# example.net
KiCad netlist of a schematic drawn in EAGLE
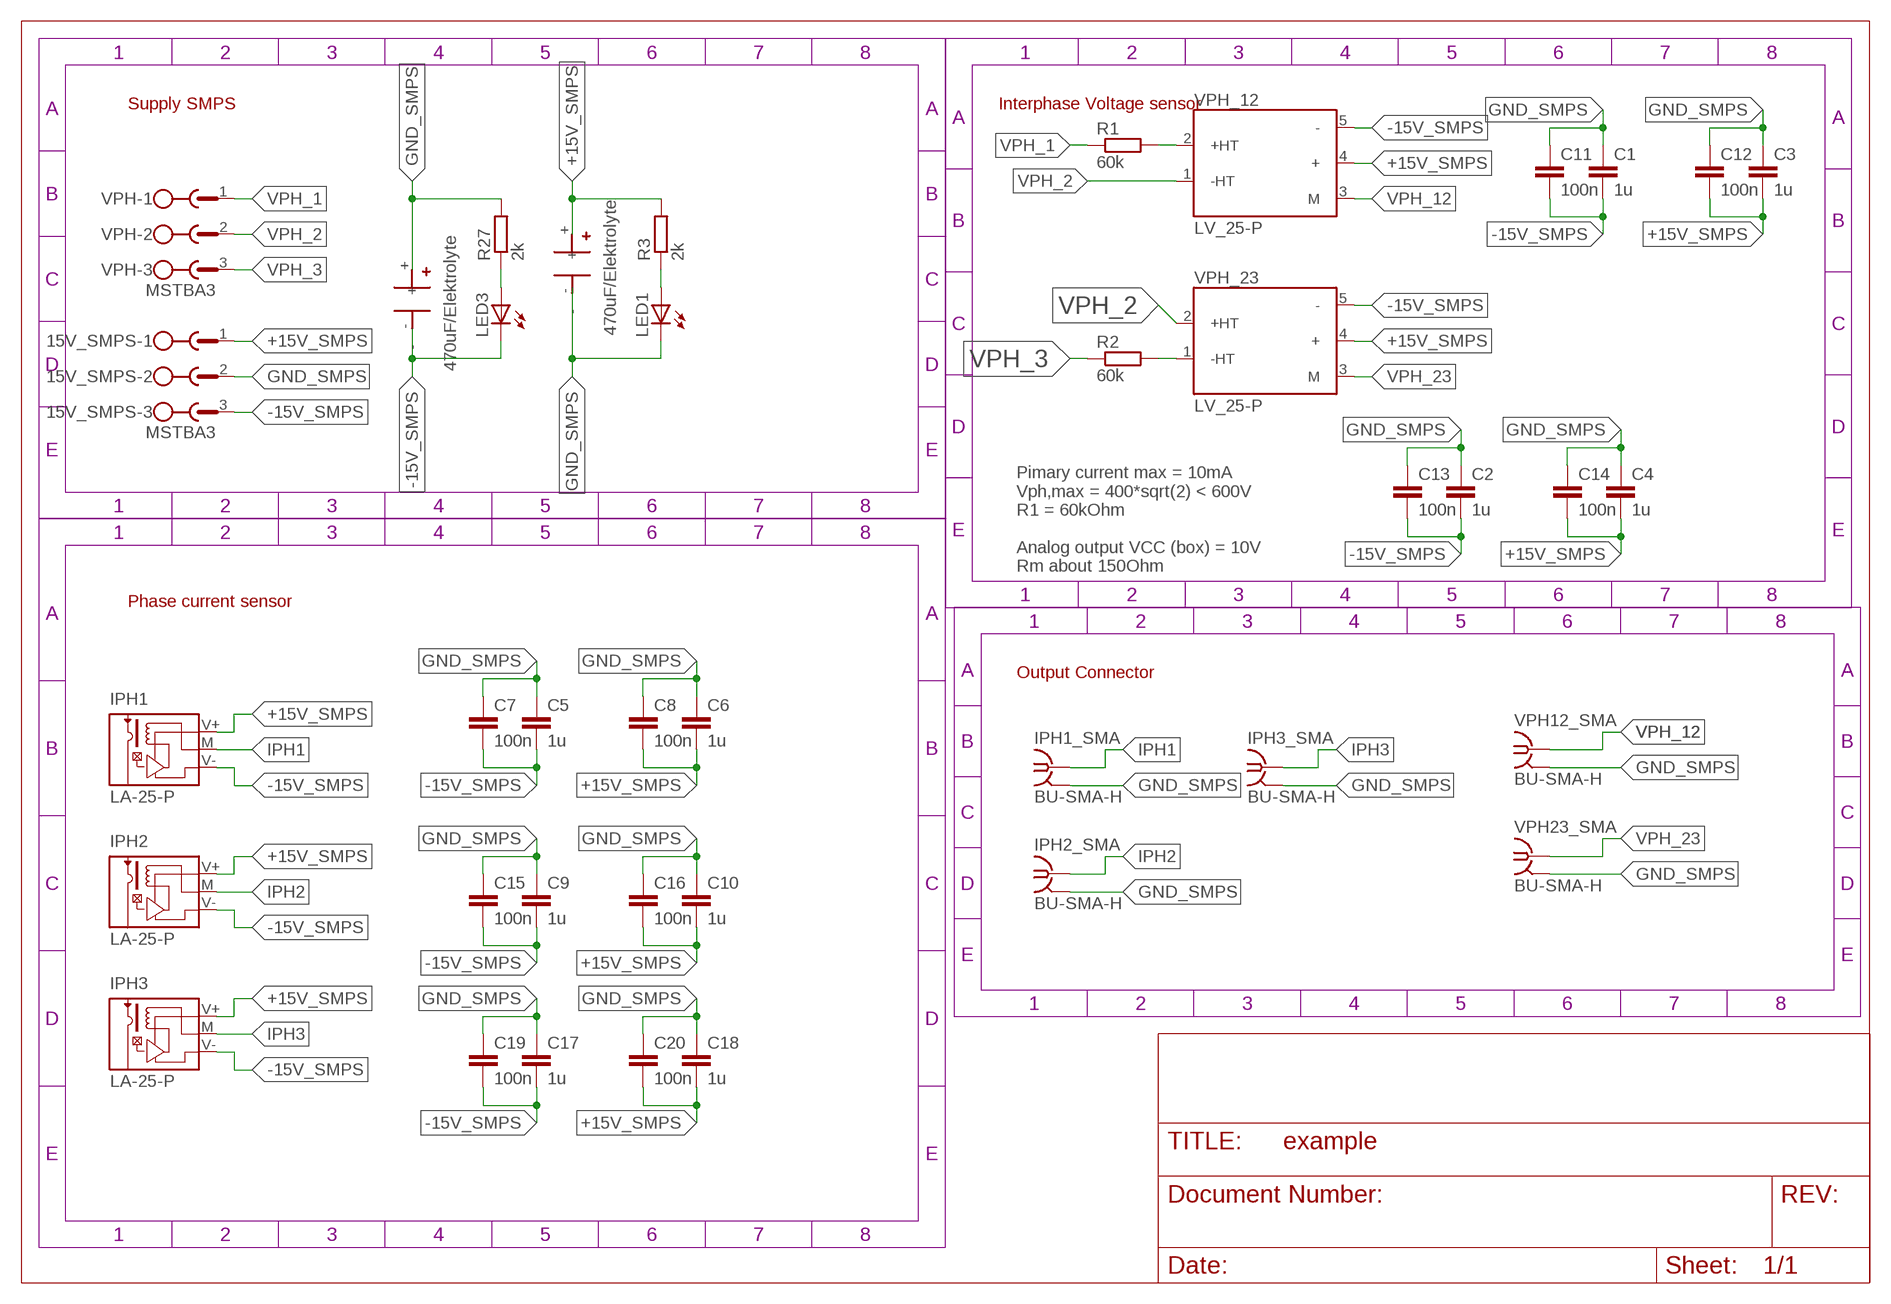
[diagram p0: schematic, sheet 1]

(export (version "E")
  (design (tool "Eeschema 10.0.6"))
  (components
    (comp (ref "15V_SMPS")
      (value "MSTBA3")
      (footprint "eagle-import:MSTBA3")
      (fields (field (name "MF") "FARNELL") (field (name "MPN") "1757255"))
      (libsource (lib "eagle-import") (part "MSTBA3"))
    )
    (comp (ref "C1")
      (value "1u")
      (footprint "eagle-import:C0805")
      (libsource (lib "eagle-import") (part "C-EUC0805"))
    )
    (comp (ref "C2")
      (value "1u")
      (footprint "eagle-import:C0805")
      (libsource (lib "eagle-import") (part "C-EUC0805"))
    )
    (comp (ref "C3")
      (value "1u")
      (footprint "eagle-import:C0805")
      (libsource (lib "eagle-import") (part "C-EUC0805"))
    )
    (comp (ref "C4")
      (value "1u")
      (footprint "eagle-import:C0805")
      (libsource (lib "eagle-import") (part "C-EUC0805"))
    )
    (comp (ref "C5")
      (value "1u")
      (footprint "eagle-import:C0805")
      (libsource (lib "eagle-import") (part "C-EUC0805"))
    )
    (comp (ref "C6")
      (value "1u")
      (footprint "eagle-import:C0805")
      (libsource (lib "eagle-import") (part "C-EUC0805"))
    )
    (comp (ref "C7")
      (value "100n")
      (footprint "eagle-import:C0805")
      (libsource (lib "eagle-import") (part "C-EUC0805"))
    )
    (comp (ref "C8")
      (value "100n")
      (footprint "eagle-import:C0805")
      (libsource (lib "eagle-import") (part "C-EUC0805"))
    )
    (comp (ref "C9")
      (value "1u")
      (footprint "eagle-import:C0805")
      (libsource (lib "eagle-import") (part "C-EUC0805"))
    )
    (comp (ref "C10")
      (value "1u")
      (footprint "eagle-import:C0805")
      (libsource (lib "eagle-import") (part "C-EUC0805"))
    )
    (comp (ref "C11")
      (value "100n")
      (footprint "eagle-import:C0805")
      (libsource (lib "eagle-import") (part "C-EUC0805"))
    )
    (comp (ref "C12")
      (value "100n")
      (footprint "eagle-import:C0805")
      (libsource (lib "eagle-import") (part "C-EUC0805"))
    )
    (comp (ref "C13")
      (value "100n")
      (footprint "eagle-import:C0805")
      (libsource (lib "eagle-import") (part "C-EUC0805"))
    )
    (comp (ref "C14")
      (value "100n")
      (footprint "eagle-import:C0805")
      (libsource (lib "eagle-import") (part "C-EUC0805"))
    )
    (comp (ref "C15")
      (value "100n")
      (footprint "eagle-import:C0805")
      (libsource (lib "eagle-import") (part "C-EUC0805"))
    )
    (comp (ref "C16")
      (value "100n")
      (footprint "eagle-import:C0805")
      (libsource (lib "eagle-import") (part "C-EUC0805"))
    )
    (comp (ref "C17")
      (value "1u")
      (footprint "eagle-import:C0805")
      (libsource (lib "eagle-import") (part "C-EUC0805"))
    )
    (comp (ref "C18")
      (value "1u")
      (footprint "eagle-import:C0805")
      (libsource (lib "eagle-import") (part "C-EUC0805"))
    )
    (comp (ref "C19")
      (value "100n")
      (footprint "eagle-import:C0805")
      (libsource (lib "eagle-import") (part "C-EUC0805"))
    )
    (comp (ref "C20")
      (value "100n")
      (footprint "eagle-import:C0805")
      (libsource (lib "eagle-import") (part "C-EUC0805"))
    )
    (comp (ref "IPH1")
      (value "LA-25-P")
      (footprint "eagle-import:LA25P")
      (libsource (lib "eagle-import") (part "LA-25-P"))
    )
    (comp (ref "IPH1_SMA")
      (value "BU-SMA-H")
      (footprint "eagle-import:BU-SMA-H")
      (libsource (lib "eagle-import") (part "BU-SMA-H"))
    )
    (comp (ref "IPH2")
      (value "LA-25-P")
      (footprint "eagle-import:LA25P")
      (libsource (lib "eagle-import") (part "LA-25-P"))
    )
    (comp (ref "IPH2_SMA")
      (value "BU-SMA-H")
      (footprint "eagle-import:BU-SMA-H")
      (libsource (lib "eagle-import") (part "BU-SMA-H"))
    )
    (comp (ref "IPH3")
      (value "LA-25-P")
      (footprint "eagle-import:LA25P")
      (libsource (lib "eagle-import") (part "LA-25-P"))
    )
    (comp (ref "IPH3_SMA")
      (value "BU-SMA-H")
      (footprint "eagle-import:BU-SMA-H")
      (libsource (lib "eagle-import") (part "BU-SMA-H"))
    )
    (comp (ref "LED1")
      (value "LEDCHIPLED_0805")
      (footprint "eagle-import:CHIPLED_0805")
      (libsource (lib "eagle-import") (part "LEDCHIPLED_0805"))
    )
    (comp (ref "LED3")
      (value "LEDCHIPLED_0805")
      (footprint "eagle-import:CHIPLED_0805")
      (libsource (lib "eagle-import") (part "LEDCHIPLED_0805"))
    )
    (comp (ref "R1")
      (value "60k")
      (footprint "eagle-import:0414_15")
      (libsource (lib "eagle-import") (part "R-EU_0414/15"))
    )
    (comp (ref "R2")
      (value "60k")
      (footprint "eagle-import:0414_15")
      (libsource (lib "eagle-import") (part "R-EU_0414/15"))
    )
    (comp (ref "R3")
      (value "2k")
      (footprint "eagle-import:R0805")
      (libsource (lib "eagle-import") (part "R-EU_R0805"))
    )
    (comp (ref "R27")
      (value "2k")
      (footprint "eagle-import:R0805")
      (libsource (lib "eagle-import") (part "R-EU_R0805"))
    )
    (comp (ref "U$1")
      (value "ELE_C_470UF_PAN")
      (footprint "eagle-import:ELEK_C_470UF_PAN")
      (libsource (lib "eagle-import") (part "ELE_C_470UF_PAN"))
    )
    (comp (ref "U$2")
      (value "ELE_C_470UF_PAN")
      (footprint "eagle-import:ELEK_C_470UF_PAN")
      (libsource (lib "eagle-import") (part "ELE_C_470UF_PAN"))
    )
    (comp (ref "VPH")
      (value "MSTBA3")
      (footprint "eagle-import:MSTBA3")
      (fields (field (name "MF") "FARNELL") (field (name "MPN") "1757255"))
      (libsource (lib "eagle-import") (part "MSTBA3"))
    )
    (comp (ref "VPH12_SMA")
      (value "BU-SMA-H")
      (footprint "eagle-import:BU-SMA-H")
      (libsource (lib "eagle-import") (part "BU-SMA-H"))
    )
    (comp (ref "VPH23_SMA")
      (value "BU-SMA-H")
      (footprint "eagle-import:BU-SMA-H")
      (libsource (lib "eagle-import") (part "BU-SMA-H"))
    )
    (comp (ref "VPH_12")
      (value "LV_25-P")
      (footprint "eagle-import:XDCR_LV25-P")
      (fields
        (field (name "DIGI-KEY_PART_NUMBER") "398-1019-ND")
        (field (name "MF") "LEM USA")
        (field (name "MP") "LV 25-P")
      )
      (libsource (lib "eagle-import") (part "LV_25-P"))
    )
    (comp (ref "VPH_23")
      (value "LV_25-P")
      (footprint "eagle-import:XDCR_LV25-P")
      (fields
        (field (name "DIGI-KEY_PART_NUMBER") "398-1019-ND")
        (field (name "MF") "LEM USA")
        (field (name "MP") "LV 25-P")
      )
      (libsource (lib "eagle-import") (part "LV_25-P"))
    )
  )
  (nets
    (net (code "1") (name "+15V_SMPS") (class "Default")
      (node (ref "15V_SMPS") (pin "1") (pinfunction "1_1") (pintype "passive"))
      (node (ref "C10") (pin "2") (pinfunction "2_2") (pintype "passive"))
      (node (ref "C12") (pin "2") (pinfunction "2_2") (pintype "passive"))
      (node (ref "C14") (pin "2") (pinfunction "2_2") (pintype "passive"))
      (node (ref "C16") (pin "2") (pinfunction "2_2") (pintype "passive"))
      (node (ref "C18") (pin "2") (pinfunction "2_2") (pintype "passive"))
      (node (ref "C20") (pin "2") (pinfunction "2_2") (pintype "passive"))
      (node (ref "C3") (pin "2") (pinfunction "2_2") (pintype "passive"))
      (node (ref "C4") (pin "2") (pinfunction "2_2") (pintype "passive"))
      (node (ref "C6") (pin "2") (pinfunction "2_2") (pintype "passive"))
      (node (ref "C8") (pin "2") (pinfunction "2_2") (pintype "passive"))
      (node (ref "IPH1") (pin "V+") (pinfunction "V+_V+") (pintype "input"))
      (node (ref "IPH2") (pin "V+") (pinfunction "V+_V+") (pintype "input"))
      (node (ref "IPH3") (pin "V+") (pinfunction "V+_V+") (pintype "input"))
      (node (ref "R3") (pin "2") (pinfunction "2_2") (pintype "passive"))
      (node (ref "U$2") (pin "+") (pinfunction "+_+") (pintype "bidirectional"))
      (node (ref "VPH_12") (pin "4") (pinfunction "+_4") (pintype "output"))
      (node (ref "VPH_23") (pin "4") (pinfunction "+_4") (pintype "output"))
    )
    (net (code "2") (name "-15V_SMPS") (class "Default")
      (node (ref "15V_SMPS") (pin "3") (pinfunction "1_3") (pintype "passive"))
      (node (ref "C1") (pin "2") (pinfunction "2_2") (pintype "passive"))
      (node (ref "C11") (pin "2") (pinfunction "2_2") (pintype "passive"))
      (node (ref "C13") (pin "2") (pinfunction "2_2") (pintype "passive"))
      (node (ref "C15") (pin "2") (pinfunction "2_2") (pintype "passive"))
      (node (ref "C17") (pin "2") (pinfunction "2_2") (pintype "passive"))
      (node (ref "C19") (pin "2") (pinfunction "2_2") (pintype "passive"))
      (node (ref "C2") (pin "2") (pinfunction "2_2") (pintype "passive"))
      (node (ref "C5") (pin "2") (pinfunction "2_2") (pintype "passive"))
      (node (ref "C7") (pin "2") (pinfunction "2_2") (pintype "passive"))
      (node (ref "C9") (pin "2") (pinfunction "2_2") (pintype "passive"))
      (node (ref "IPH1") (pin "V-") (pinfunction "V-_V-") (pintype "input"))
      (node (ref "IPH2") (pin "V-") (pinfunction "V-_V-") (pintype "input"))
      (node (ref "IPH3") (pin "V-") (pinfunction "V-_V-") (pintype "input"))
      (node (ref "LED3") (pin "C") (pinfunction "C_C") (pintype "passive"))
      (node (ref "U$1") (pin "-") (pinfunction "-_-") (pintype "bidirectional"))
      (node (ref "VPH_12") (pin "5") (pinfunction "-_5") (pintype "output"))
      (node (ref "VPH_23") (pin "5") (pinfunction "-_5") (pintype "output"))
    )
    (net (code "3") (name "GND_SMPS") (class "Default")
      (node (ref "15V_SMPS") (pin "2") (pinfunction "1_2") (pintype "passive"))
      (node (ref "C1") (pin "1") (pinfunction "1_1") (pintype "passive"))
      (node (ref "C10") (pin "1") (pinfunction "1_1") (pintype "passive"))
      (node (ref "C11") (pin "1") (pinfunction "1_1") (pintype "passive"))
      (node (ref "C12") (pin "1") (pinfunction "1_1") (pintype "passive"))
      (node (ref "C13") (pin "1") (pinfunction "1_1") (pintype "passive"))
      (node (ref "C14") (pin "1") (pinfunction "1_1") (pintype "passive"))
      (node (ref "C15") (pin "1") (pinfunction "1_1") (pintype "passive"))
      (node (ref "C16") (pin "1") (pinfunction "1_1") (pintype "passive"))
      (node (ref "C17") (pin "1") (pinfunction "1_1") (pintype "passive"))
      (node (ref "C18") (pin "1") (pinfunction "1_1") (pintype "passive"))
      (node (ref "C19") (pin "1") (pinfunction "1_1") (pintype "passive"))
      (node (ref "C2") (pin "1") (pinfunction "1_1") (pintype "passive"))
      (node (ref "C20") (pin "1") (pinfunction "1_1") (pintype "passive"))
      (node (ref "C3") (pin "1") (pinfunction "1_1") (pintype "passive"))
      (node (ref "C4") (pin "1") (pinfunction "1_1") (pintype "passive"))
      (node (ref "C5") (pin "1") (pinfunction "1_1") (pintype "passive"))
      (node (ref "C6") (pin "1") (pinfunction "1_1") (pintype "passive"))
      (node (ref "C7") (pin "1") (pinfunction "1_1") (pintype "passive"))
      (node (ref "C8") (pin "1") (pinfunction "1_1") (pintype "passive"))
      (node (ref "C9") (pin "1") (pinfunction "1_1") (pintype "passive"))
      (node (ref "IPH1_SMA") (pin "2") (pinfunction "2_2") (pintype "passive"))
      (node (ref "IPH1_SMA") (pin "3") (pinfunction "2_3") (pintype "passive"))
      (node (ref "IPH1_SMA") (pin "4") (pinfunction "2_4") (pintype "passive"))
      (node (ref "IPH1_SMA") (pin "5") (pinfunction "2_5") (pintype "passive"))
      (node (ref "IPH2_SMA") (pin "2") (pinfunction "2_2") (pintype "passive"))
      (node (ref "IPH2_SMA") (pin "3") (pinfunction "2_3") (pintype "passive"))
      (node (ref "IPH2_SMA") (pin "4") (pinfunction "2_4") (pintype "passive"))
      (node (ref "IPH2_SMA") (pin "5") (pinfunction "2_5") (pintype "passive"))
      (node (ref "IPH3_SMA") (pin "2") (pinfunction "2_2") (pintype "passive"))
      (node (ref "IPH3_SMA") (pin "3") (pinfunction "2_3") (pintype "passive"))
      (node (ref "IPH3_SMA") (pin "4") (pinfunction "2_4") (pintype "passive"))
      (node (ref "IPH3_SMA") (pin "5") (pinfunction "2_5") (pintype "passive"))
      (node (ref "LED1") (pin "C") (pinfunction "C_C") (pintype "passive"))
      (node (ref "R27") (pin "2") (pinfunction "2_2") (pintype "passive"))
      (node (ref "U$1") (pin "+") (pinfunction "+_+") (pintype "bidirectional"))
      (node (ref "U$2") (pin "-") (pinfunction "-_-") (pintype "bidirectional"))
      (node (ref "VPH12_SMA") (pin "2") (pinfunction "2_2") (pintype "passive"))
      (node (ref "VPH12_SMA") (pin "3") (pinfunction "2_3") (pintype "passive"))
      (node (ref "VPH12_SMA") (pin "4") (pinfunction "2_4") (pintype "passive"))
      (node (ref "VPH12_SMA") (pin "5") (pinfunction "2_5") (pintype "passive"))
      (node (ref "VPH23_SMA") (pin "2") (pinfunction "2_2") (pintype "passive"))
      (node (ref "VPH23_SMA") (pin "3") (pinfunction "2_3") (pintype "passive"))
      (node (ref "VPH23_SMA") (pin "4") (pinfunction "2_4") (pintype "passive"))
      (node (ref "VPH23_SMA") (pin "5") (pinfunction "2_5") (pintype "passive"))
    )
    (net (code "4") (name "IPH1") (class "Default")
      (node (ref "IPH1") (pin "M") (pinfunction "M_M") (pintype "output"))
      (node (ref "IPH1_SMA") (pin "1") (pinfunction "1_1") (pintype "passive"))
    )
    (net (code "5") (name "IPH2") (class "Default")
      (node (ref "IPH2") (pin "M") (pinfunction "M_M") (pintype "output"))
      (node (ref "IPH2_SMA") (pin "1") (pinfunction "1_1") (pintype "passive"))
    )
    (net (code "6") (name "IPH3") (class "Default")
      (node (ref "IPH3") (pin "M") (pinfunction "M_M") (pintype "output"))
      (node (ref "IPH3_SMA") (pin "1") (pinfunction "1_1") (pintype "passive"))
    )
    (net (code "7") (name "Net-(LED1-PadA)") (class "Default")
      (node (ref "LED1") (pin "A") (pinfunction "A_A") (pintype "passive"))
      (node (ref "R3") (pin "1") (pinfunction "1_1") (pintype "passive"))
    )
    (net (code "8") (name "Net-(LED3-PadA)") (class "Default")
      (node (ref "LED3") (pin "A") (pinfunction "A_A") (pintype "passive"))
      (node (ref "R27") (pin "1") (pinfunction "1_1") (pintype "passive"))
    )
    (net (code "9") (name "Net-(VPH_12-+HT)") (class "Default")
      (node (ref "R1") (pin "2") (pinfunction "2_2") (pintype "passive"))
      (node (ref "VPH_12") (pin "2") (pinfunction "+HT_2") (pintype "input"))
    )
    (net (code "10") (name "Net-(VPH_23--HT)") (class "Default")
      (node (ref "R2") (pin "2") (pinfunction "2_2") (pintype "passive"))
      (node (ref "VPH_23") (pin "1") (pinfunction "-HT_1") (pintype "input"))
    )
    (net (code "11") (name "VPH_1") (class "Default")
      (node (ref "R1") (pin "1") (pinfunction "1_1") (pintype "passive"))
      (node (ref "VPH") (pin "1") (pinfunction "1_1") (pintype "passive"))
    )
    (net (code "12") (name "VPH_2") (class "Default")
      (node (ref "VPH") (pin "2") (pinfunction "1_2") (pintype "passive"))
      (node (ref "VPH_12") (pin "1") (pinfunction "-HT_1") (pintype "input"))
      (node (ref "VPH_23") (pin "2") (pinfunction "+HT_2") (pintype "input"))
    )
    (net (code "13") (name "VPH_3") (class "Default")
      (node (ref "R2") (pin "1") (pinfunction "1_1") (pintype "passive"))
      (node (ref "VPH") (pin "3") (pinfunction "1_3") (pintype "passive"))
    )
    (net (code "14") (name "VPH_12") (class "Default")
      (node (ref "VPH12_SMA") (pin "1") (pinfunction "1_1") (pintype "passive"))
      (node (ref "VPH_12") (pin "3") (pinfunction "M_3") (pintype "output"))
    )
    (net (code "15") (name "VPH_23") (class "Default")
      (node (ref "VPH23_SMA") (pin "1") (pinfunction "1_1") (pintype "passive"))
      (node (ref "VPH_23") (pin "3") (pinfunction "M_3") (pintype "output"))
    )
  )
)
